# FeatherAzureSphereLongTall.net
KiCad netlist of a schematic drawn in EAGLE
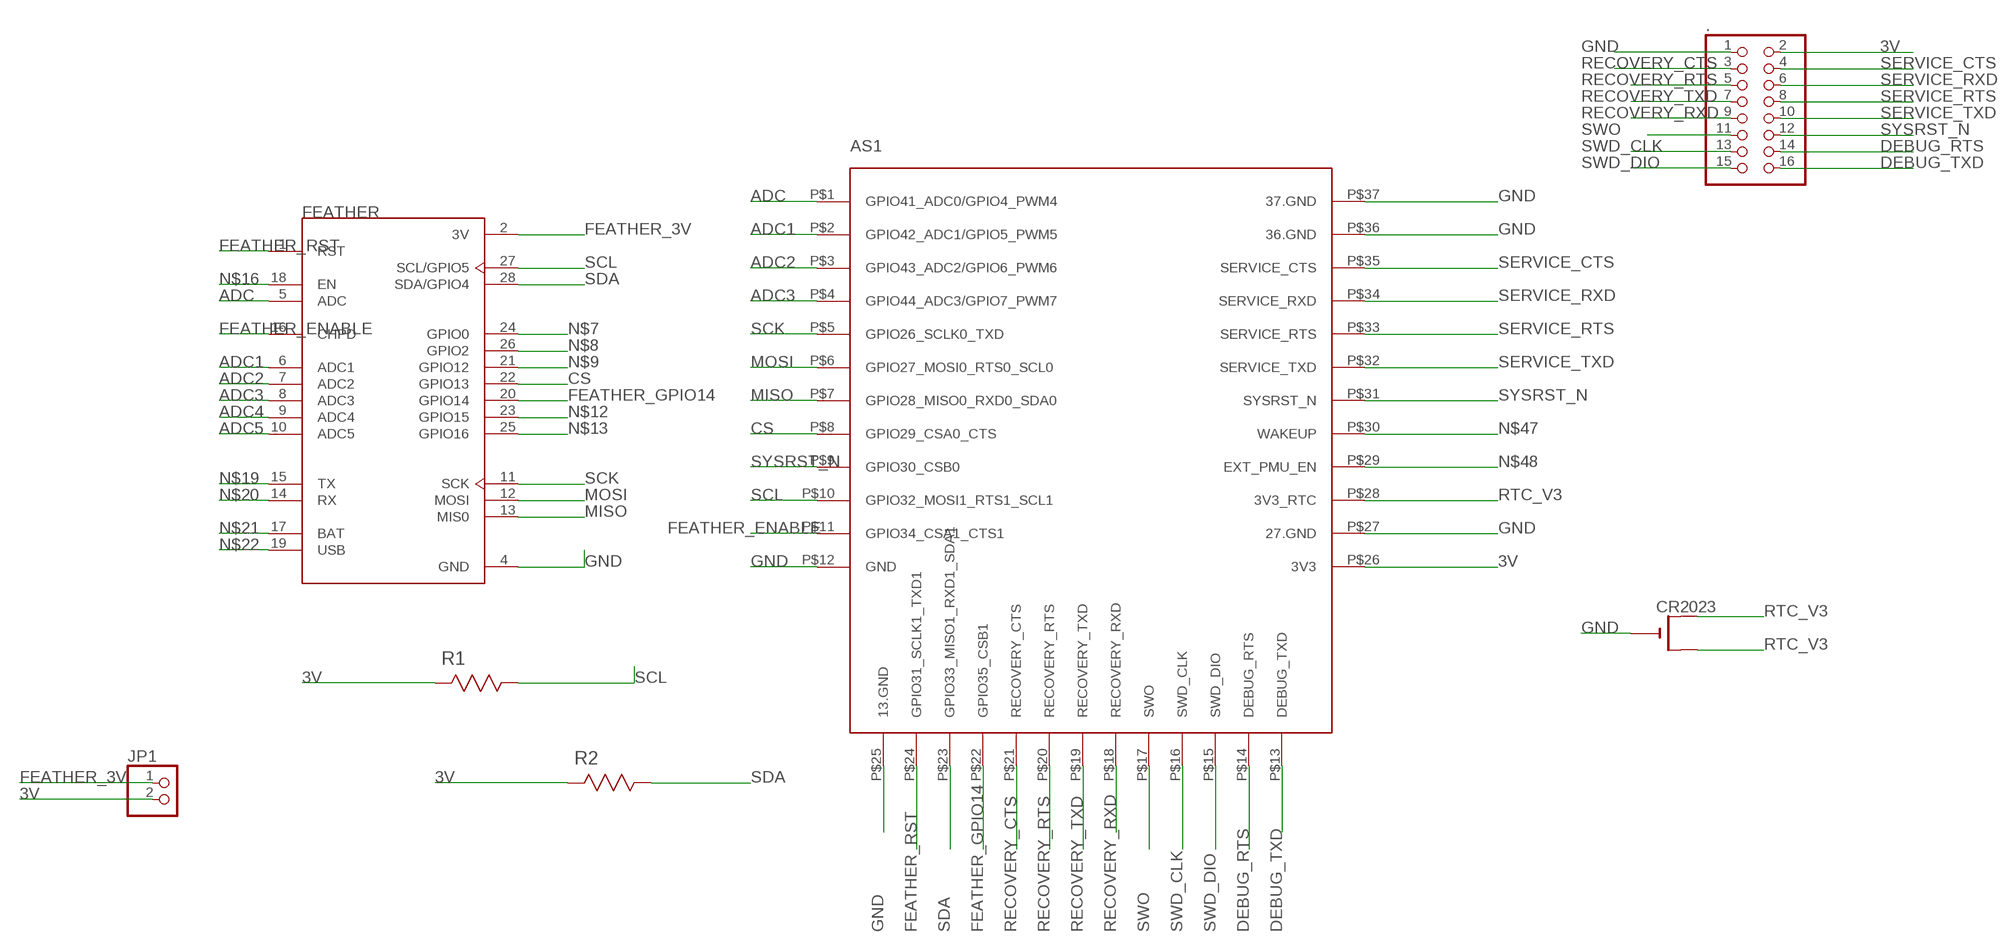
[diagram p0: schematic, sheet 1]

(export (version "E")
  (design (tool "Eeschema 10.0.6"))
  (components
    (comp (ref ".")
      (value "PINHD-2X8")
      (footprint "eagle-import:2X08")
      (libsource (lib "eagle-import") (part "PINHD-2X8"))
    )
    (comp (ref "AS1")
      (value "WF-M620-RSC1")
      (footprint "eagle-import:WF-M620-RSC1")
      (libsource (lib "eagle-import") (part "WF-M620-RSC1"))
    )
    (comp (ref "CR2023")
      (value "CR2032SMT")
      (footprint "eagle-import:CR2032-SMD")
      (libsource (lib "eagle-import") (part "CR2032SMT"))
    )
    (comp (ref "FEATHER")
      (value "2821")
      (footprint "eagle-import:XCVR_2821")
      (fields (field (name "MF") "Adafruit Industries"))
      (libsource (lib "eagle-import") (part "2821"))
    )
    (comp (ref "JP1")
      (value "PINHD-1X2")
      (footprint "eagle-import:1X02")
      (libsource (lib "eagle-import") (part "PINHD-1X2"))
    )
    (comp (ref "R1")
      (value "ERJ-8RQF1R5V")
      (footprint "eagle-import:RESC3216X71N")
      (fields (field (name "TOLERANCE") "±1 %"))
      (libsource (lib "eagle-import") (part "ERJ-8RQF1R5V"))
    )
    (comp (ref "R2")
      (value "ERJ-8RQF1R5V")
      (footprint "eagle-import:RESC3216X71N")
      (fields (field (name "TOLERANCE") "±1 %"))
      (libsource (lib "eagle-import") (part "ERJ-8RQF1R5V"))
    )
  )
  (nets
    (net (code "1") (name "/3V") (class "Default")
      (node (ref ".") (pin "2") (pinfunction "2_2") (pintype "passive"))
      (node (ref "AS1") (pin "P$26") (pinfunction "3V3_P$26") (pintype "bidirectional"))
      (node (ref "JP1") (pin "2") (pinfunction "2_2") (pintype "passive"))
      (node (ref "R1") (pin "2") (pinfunction "R2_2") (pintype "passive"))
      (node (ref "R2") (pin "2") (pinfunction "R2_2") (pintype "passive"))
    )
    (net (code "2") (name "/ADC") (class "Default")
      (node (ref "AS1") (pin "P$1") (pinfunction "GPIO41_ADC0/GPIO4_PWM4_P$1") (pintype "bidirectional"))
      (node (ref "FEATHER") (pin "5") (pinfunction "ADC_5") (pintype "bidirectional"))
    )
    (net (code "3") (name "/ADC1") (class "Default")
      (node (ref "AS1") (pin "P$2") (pinfunction "GPIO42_ADC1/GPIO5_PWM5_P$2") (pintype "bidirectional"))
      (node (ref "FEATHER") (pin "6") (pinfunction "ADC1_6") (pintype "bidirectional"))
    )
    (net (code "4") (name "/ADC2") (class "Default")
      (node (ref "AS1") (pin "P$3") (pinfunction "GPIO43_ADC2/GPIO6_PWM6_P$3") (pintype "bidirectional"))
      (node (ref "FEATHER") (pin "7") (pinfunction "ADC2_7") (pintype "bidirectional"))
    )
    (net (code "5") (name "/ADC3") (class "Default")
      (node (ref "AS1") (pin "P$4") (pinfunction "GPIO44_ADC3/GPIO7_PWM7_P$4") (pintype "bidirectional"))
      (node (ref "FEATHER") (pin "8") (pinfunction "ADC3_8") (pintype "bidirectional"))
    )
    (net (code "6") (name "/ADC4") (class "Default")
      (node (ref "FEATHER") (pin "9") (pinfunction "ADC4_9") (pintype "bidirectional"))
    )
    (net (code "7") (name "/ADC5") (class "Default")
      (node (ref "FEATHER") (pin "10") (pinfunction "ADC5_10") (pintype "bidirectional"))
    )
    (net (code "8") (name "/CS") (class "Default")
      (node (ref "AS1") (pin "P$8") (pinfunction "GPIO29_CSA0_CTS_P$8") (pintype "bidirectional"))
      (node (ref "FEATHER") (pin "22") (pinfunction "GPIO13_22") (pintype "bidirectional"))
    )
    (net (code "9") (name "/DEBUG_RTS") (class "Default")
      (node (ref ".") (pin "14") (pinfunction "14_14") (pintype "passive"))
      (node (ref "AS1") (pin "P$14") (pinfunction "DEBUG_RTS_P$14") (pintype "bidirectional"))
    )
    (net (code "10") (name "/DEBUG_TXD") (class "Default")
      (node (ref ".") (pin "16") (pinfunction "16_16") (pintype "passive"))
      (node (ref "AS1") (pin "P$13") (pinfunction "DEBUG_TXD_P$13") (pintype "bidirectional"))
    )
    (net (code "11") (name "/FEATHER_3V") (class "Default")
      (node (ref "FEATHER") (pin "2") (pinfunction "3V_2") (pintype "power_in"))
      (node (ref "JP1") (pin "1") (pinfunction "1_1") (pintype "passive"))
    )
    (net (code "12") (name "/FEATHER_ENABLE") (class "Default")
      (node (ref "AS1") (pin "P$11") (pinfunction "GPIO34_CSA1_CTS1_P$11") (pintype "bidirectional"))
      (node (ref "FEATHER") (pin "16") (pinfunction "CHPD_16") (pintype "bidirectional"))
    )
    (net (code "13") (name "/FEATHER_GPIO14") (class "Default")
      (node (ref "AS1") (pin "P$22") (pinfunction "GPIO35_CSB1_P$22") (pintype "bidirectional"))
      (node (ref "FEATHER") (pin "20") (pinfunction "GPIO14_20") (pintype "bidirectional"))
    )
    (net (code "14") (name "/FEATHER_RST") (class "Default")
      (node (ref "AS1") (pin "P$24") (pinfunction "GPIO31_SCLK1_TXD1_P$24") (pintype "bidirectional"))
      (node (ref "FEATHER") (pin "1") (pinfunction "RST_1") (pintype "input"))
    )
    (net (code "15") (name "/GND") (class "Default")
      (node (ref ".") (pin "1") (pinfunction "1_1") (pintype "passive"))
      (node (ref "AS1") (pin "P$12") (pinfunction "GND_P$12") (pintype "bidirectional"))
      (node (ref "AS1") (pin "P$25") (pinfunction "13.GND_P$25") (pintype "bidirectional"))
      (node (ref "AS1") (pin "P$27") (pinfunction "27.GND_P$27") (pintype "bidirectional"))
      (node (ref "AS1") (pin "P$36") (pinfunction "36.GND_P$36") (pintype "bidirectional"))
      (node (ref "AS1") (pin "P$37") (pinfunction "37.GND_P$37") (pintype "bidirectional"))
      (node (ref "CR2023") (pin "-") (pinfunction "-_-") (pintype "passive"))
      (node (ref "FEATHER") (pin "4") (pinfunction "GND_4") (pintype "power_in"))
    )
    (net (code "16") (name "/MISO") (class "Default")
      (node (ref "AS1") (pin "P$7") (pinfunction "GPIO28_MISO0_RXD0_SDA0_P$7") (pintype "bidirectional"))
      (node (ref "FEATHER") (pin "13") (pinfunction "MIS0_13") (pintype "input"))
    )
    (net (code "17") (name "/MOSI") (class "Default")
      (node (ref "AS1") (pin "P$6") (pinfunction "GPIO27_MOSI0_RTS0_SCL0_P$6") (pintype "bidirectional"))
      (node (ref "FEATHER") (pin "12") (pinfunction "MOSI_12") (pintype "output"))
    )
    (net (code "18") (name "/N$7") (class "Default")
      (node (ref "FEATHER") (pin "24") (pinfunction "GPIO0_24") (pintype "bidirectional"))
    )
    (net (code "19") (name "/N$8") (class "Default")
      (node (ref "FEATHER") (pin "26") (pinfunction "GPIO2_26") (pintype "bidirectional"))
    )
    (net (code "20") (name "/N$9") (class "Default")
      (node (ref "FEATHER") (pin "21") (pinfunction "GPIO12_21") (pintype "bidirectional"))
    )
    (net (code "21") (name "/N$12") (class "Default")
      (node (ref "FEATHER") (pin "23") (pinfunction "GPIO15_23") (pintype "bidirectional"))
    )
    (net (code "22") (name "/N$13") (class "Default")
      (node (ref "FEATHER") (pin "25") (pinfunction "GPIO16_25") (pintype "bidirectional"))
    )
    (net (code "23") (name "/N$16") (class "Default")
      (node (ref "FEATHER") (pin "18") (pinfunction "EN_18") (pintype "input"))
    )
    (net (code "24") (name "/N$19") (class "Default")
      (node (ref "FEATHER") (pin "15") (pinfunction "TX_15") (pintype "output"))
    )
    (net (code "25") (name "/N$20") (class "Default")
      (node (ref "FEATHER") (pin "14") (pinfunction "RX_14") (pintype "input"))
    )
    (net (code "26") (name "/N$21") (class "Default")
      (node (ref "FEATHER") (pin "17") (pinfunction "BAT_17") (pintype "bidirectional"))
    )
    (net (code "27") (name "/N$22") (class "Default")
      (node (ref "FEATHER") (pin "19") (pinfunction "USB_19") (pintype "bidirectional"))
    )
    (net (code "28") (name "/N$47") (class "Default")
      (node (ref "AS1") (pin "P$30") (pinfunction "WAKEUP_P$30") (pintype "bidirectional"))
    )
    (net (code "29") (name "/N$48") (class "Default")
      (node (ref "AS1") (pin "P$29") (pinfunction "EXT_PMU_EN_P$29") (pintype "bidirectional"))
    )
    (net (code "30") (name "/RECOVERY_CTS") (class "Default")
      (node (ref ".") (pin "3") (pinfunction "3_3") (pintype "passive"))
      (node (ref "AS1") (pin "P$21") (pinfunction "RECOVERY_CTS_P$21") (pintype "bidirectional"))
    )
    (net (code "31") (name "/RECOVERY_RTS") (class "Default")
      (node (ref ".") (pin "5") (pinfunction "5_5") (pintype "passive"))
      (node (ref "AS1") (pin "P$20") (pinfunction "RECOVERY_RTS_P$20") (pintype "bidirectional"))
    )
    (net (code "32") (name "/RECOVERY_RXD") (class "Default")
      (node (ref ".") (pin "9") (pinfunction "9_9") (pintype "passive"))
      (node (ref "AS1") (pin "P$18") (pinfunction "RECOVERY_RXD_P$18") (pintype "bidirectional"))
    )
    (net (code "33") (name "/RECOVERY_TXD") (class "Default")
      (node (ref ".") (pin "7") (pinfunction "7_7") (pintype "passive"))
      (node (ref "AS1") (pin "P$19") (pinfunction "RECOVERY_TXD_P$19") (pintype "bidirectional"))
    )
    (net (code "34") (name "/RTC_V3") (class "Default")
      (node (ref "AS1") (pin "P$28") (pinfunction "3V3_RTC_P$28") (pintype "bidirectional"))
      (node (ref "CR2023") (pin "+$1") (pinfunction "+_+$1") (pintype "passive"))
      (node (ref "CR2023") (pin "+$2") (pinfunction "+1_+$2") (pintype "passive"))
    )
    (net (code "35") (name "/SCK") (class "Default")
      (node (ref "AS1") (pin "P$5") (pinfunction "GPIO26_SCLK0_TXD_P$5") (pintype "bidirectional"))
      (node (ref "FEATHER") (pin "11") (pinfunction "SCK_11") (pintype "bidirectional"))
    )
    (net (code "36") (name "/SCL") (class "Default")
      (node (ref "AS1") (pin "P$10") (pinfunction "GPIO32_MOSI1_RTS1_SCL1_P$10") (pintype "bidirectional"))
      (node (ref "FEATHER") (pin "27") (pinfunction "SCL/GPIO5_27") (pintype "bidirectional"))
      (node (ref "R1") (pin "1") (pinfunction "R1_1") (pintype "passive"))
    )
    (net (code "37") (name "/SDA") (class "Default")
      (node (ref "AS1") (pin "P$23") (pinfunction "GPIO33_MISO1_RXD1_SDA1_P$23") (pintype "bidirectional"))
      (node (ref "FEATHER") (pin "28") (pinfunction "SDA/GPIO4_28") (pintype "bidirectional"))
      (node (ref "R2") (pin "1") (pinfunction "R1_1") (pintype "passive"))
    )
    (net (code "38") (name "/SERVICE_CTS") (class "Default")
      (node (ref ".") (pin "4") (pinfunction "4_4") (pintype "passive"))
      (node (ref "AS1") (pin "P$35") (pinfunction "SERVICE_CTS_P$35") (pintype "bidirectional"))
    )
    (net (code "39") (name "/SERVICE_RTS") (class "Default")
      (node (ref ".") (pin "8") (pinfunction "8_8") (pintype "passive"))
      (node (ref "AS1") (pin "P$33") (pinfunction "SERVICE_RTS_P$33") (pintype "bidirectional"))
    )
    (net (code "40") (name "/SERVICE_RXD") (class "Default")
      (node (ref ".") (pin "6") (pinfunction "6_6") (pintype "passive"))
      (node (ref "AS1") (pin "P$34") (pinfunction "SERVICE_RXD_P$34") (pintype "bidirectional"))
    )
    (net (code "41") (name "/SERVICE_TXD") (class "Default")
      (node (ref ".") (pin "10") (pinfunction "10_10") (pintype "passive"))
      (node (ref "AS1") (pin "P$32") (pinfunction "SERVICE_TXD_P$32") (pintype "bidirectional"))
    )
    (net (code "42") (name "/SWD_CLK") (class "Default")
      (node (ref ".") (pin "13") (pinfunction "13_13") (pintype "passive"))
      (node (ref "AS1") (pin "P$16") (pinfunction "SWD_CLK_P$16") (pintype "bidirectional"))
    )
    (net (code "43") (name "/SWD_DIO") (class "Default")
      (node (ref ".") (pin "15") (pinfunction "15_15") (pintype "passive"))
      (node (ref "AS1") (pin "P$15") (pinfunction "SWD_DIO_P$15") (pintype "bidirectional"))
    )
    (net (code "44") (name "/SWO") (class "Default")
      (node (ref ".") (pin "11") (pinfunction "11_11") (pintype "passive"))
      (node (ref "AS1") (pin "P$17") (pinfunction "SWO_P$17") (pintype "bidirectional"))
    )
    (net (code "45") (name "/SYSRST_N") (class "Default")
      (node (ref ".") (pin "12") (pinfunction "12_12") (pintype "passive"))
      (node (ref "AS1") (pin "P$31") (pinfunction "SYSRST_N_P$31") (pintype "bidirectional"))
      (node (ref "AS1") (pin "P$9") (pinfunction "GPIO30_CSB0_P$9") (pintype "bidirectional"))
    )
  )
)
